# LED_Connector.net
KiCad netlist of a schematic drawn in Altium Designer
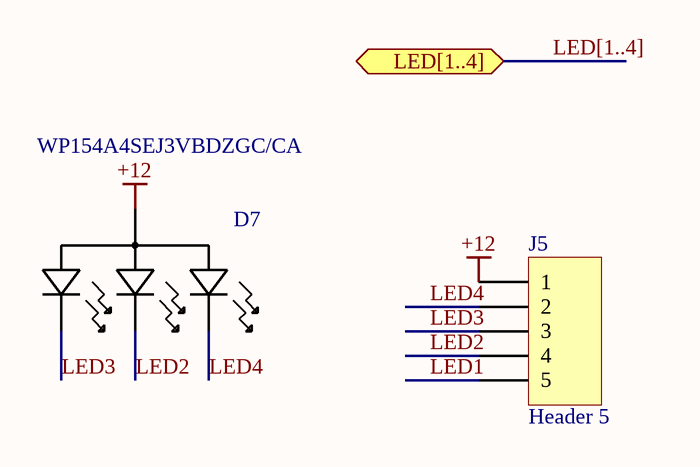
[diagram p0: LED_Connector.SchDoc]

(export (version "E")
  (design (tool "Eeschema 10.0.6"))
  (components
    (comp (ref "D7")
      (value "WP154A4SEJ3VBDZGC/CA")
      (footprint "LED_RGB_5MM")
      (description "5mm RGB Tri-Color Round Lamp")
      (fields (field (name "COPYRIGHT") "Copyright (C) 2022 Ultra Librarian. All rights reserved."))
      (libsource (lib "WP154A4SEJ3VBDZGC&slash_CA") (part "WP154A4SEJ3VBDZGC/CA"))
    )
    (comp (ref "J5")
      (value "Header 5")
      (footprint "CONN. 5")
      (fields (field (name "PUBLISHER") "Altium Limited"))
      (libsource (lib "DIY-USB Led Controller") (part "TermBlock 5"))
    )
  )
  (nets
    (net (code "1") (name "+12") (class "Default")
      (node (ref "D7") (pin "2") (pinfunction "2_2") (pintype "passive"))
      (node (ref "J5") (pin "1") (pinfunction "1_1") (pintype "passive"))
    )
    (net (code "2") (name "/LED1") (class "Default")
      (node (ref "J5") (pin "5") (pinfunction "5_5") (pintype "passive"))
    )
    (net (code "3") (name "/LED2") (class "Default")
      (node (ref "D7") (pin "3") (pinfunction "3_3") (pintype "passive"))
      (node (ref "J5") (pin "4") (pinfunction "4_4") (pintype "passive"))
    )
    (net (code "4") (name "/LED3") (class "Default")
      (node (ref "D7") (pin "1") (pinfunction "1_1") (pintype "passive"))
      (node (ref "J5") (pin "3") (pinfunction "3_3") (pintype "passive"))
    )
    (net (code "5") (name "/LED4") (class "Default")
      (node (ref "D7") (pin "4") (pinfunction "4_4") (pintype "passive"))
      (node (ref "J5") (pin "2") (pinfunction "2_2") (pintype "passive"))
    )
  )
)
